# Micro_Bit_Controller_Bit.net
KiCad netlist of a schematic drawn in EAGLE
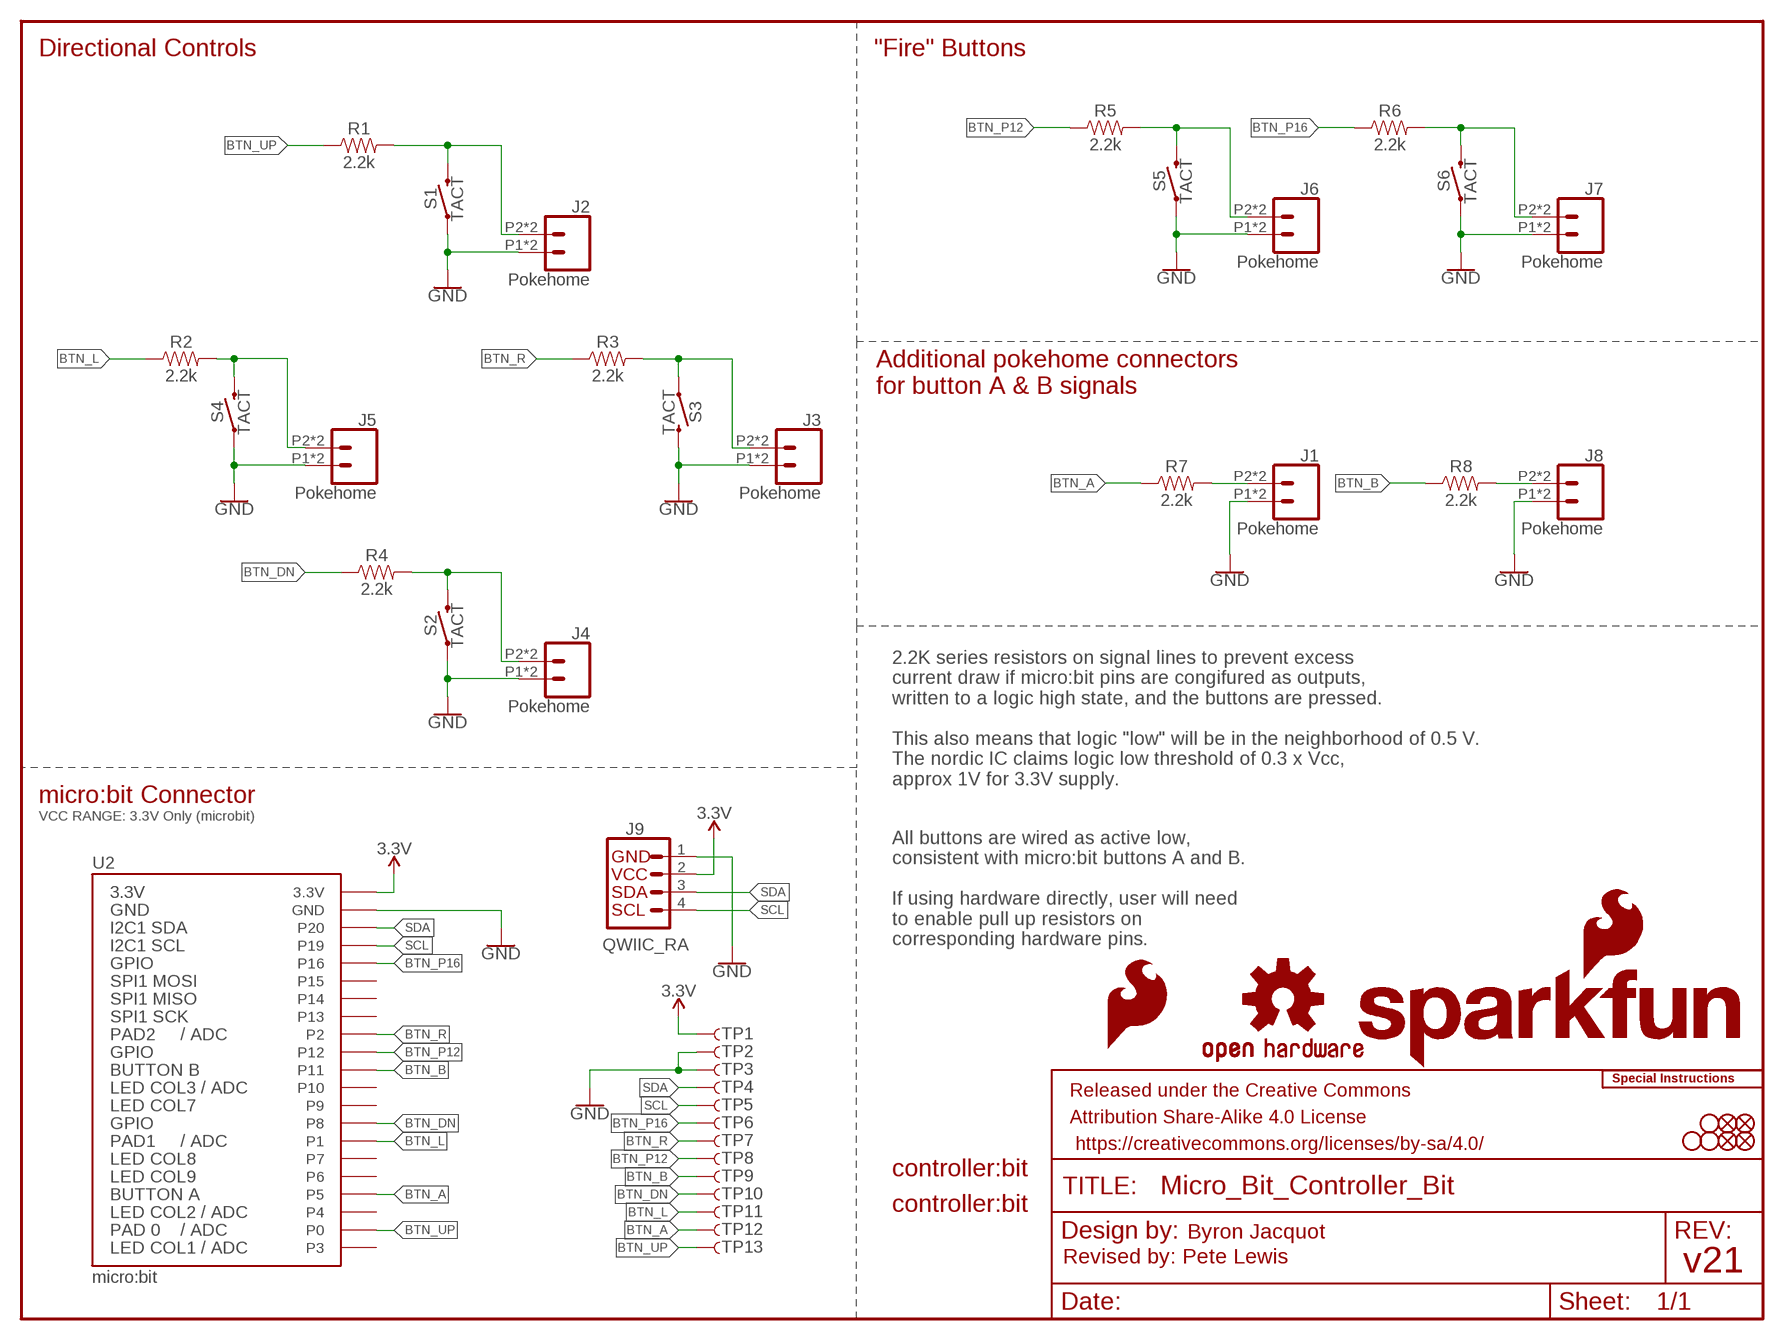
[diagram p0: schematic, sheet 1]

(export (version "E")
  (design (tool "Eeschema 10.0.6"))
  (components
    (comp (ref "FD1")
      (value "FIDUCIALUFIDUCIAL")
      (footprint "eagle-import:FIDUCIAL-MICRO")
      (libsource (lib "eagle-import") (part "FIDUCIALUFIDUCIAL"))
    )
    (comp (ref "FD2")
      (value "FIDUCIALUFIDUCIAL")
      (footprint "eagle-import:FIDUCIAL-MICRO")
      (libsource (lib "eagle-import") (part "FIDUCIALUFIDUCIAL"))
    )
    (comp (ref "FD3")
      (value "FIDUCIALUFIDUCIAL")
      (footprint "eagle-import:FIDUCIAL-MICRO")
      (libsource (lib "eagle-import") (part "FIDUCIALUFIDUCIAL"))
    )
    (comp (ref "FD4")
      (value "FIDUCIALUFIDUCIAL")
      (footprint "eagle-import:FIDUCIAL-MICRO")
      (libsource (lib "eagle-import") (part "FIDUCIALUFIDUCIAL"))
    )
    (comp (ref "FRAME1")
      (value "FRAME-LETTER")
      (footprint "eagle-import:CREATIVE_COMMONS")
      (libsource (lib "eagle-import") (part "FRAME-LETTER"))
    )
    (comp (ref "H1")
      (value "STAND-OFF")
      (footprint "eagle-import:STAND-OFF")
      (libsource (lib "eagle-import") (part "STAND-OFF"))
    )
    (comp (ref "H2")
      (value "STAND-OFF")
      (footprint "eagle-import:STAND-OFF")
      (libsource (lib "eagle-import") (part "STAND-OFF"))
    )
    (comp (ref "H3")
      (value "STAND-OFF")
      (footprint "eagle-import:STAND-OFF")
      (libsource (lib "eagle-import") (part "STAND-OFF"))
    )
    (comp (ref "J1")
      (value "Pokehome")
      (footprint "eagle-import:1X02_POKEHOME")
      (libsource (lib "eagle-import") (part "CONN_02SMALL_POKEHOME"))
    )
    (comp (ref "J2")
      (value "Pokehome")
      (footprint "eagle-import:1X02_POKEHOME")
      (libsource (lib "eagle-import") (part "CONN_02SMALL_POKEHOME"))
    )
    (comp (ref "J3")
      (value "Pokehome")
      (footprint "eagle-import:1X02_POKEHOME")
      (libsource (lib "eagle-import") (part "CONN_02SMALL_POKEHOME"))
    )
    (comp (ref "J4")
      (value "Pokehome")
      (footprint "eagle-import:1X02_POKEHOME")
      (libsource (lib "eagle-import") (part "CONN_02SMALL_POKEHOME"))
    )
    (comp (ref "J5")
      (value "Pokehome")
      (footprint "eagle-import:1X02_POKEHOME")
      (libsource (lib "eagle-import") (part "CONN_02SMALL_POKEHOME"))
    )
    (comp (ref "J6")
      (value "Pokehome")
      (footprint "eagle-import:1X02_POKEHOME")
      (libsource (lib "eagle-import") (part "CONN_02SMALL_POKEHOME"))
    )
    (comp (ref "J7")
      (value "Pokehome")
      (footprint "eagle-import:1X02_POKEHOME")
      (libsource (lib "eagle-import") (part "CONN_02SMALL_POKEHOME"))
    )
    (comp (ref "J8")
      (value "Pokehome")
      (footprint "eagle-import:1X02_POKEHOME")
      (libsource (lib "eagle-import") (part "CONN_02SMALL_POKEHOME"))
    )
    (comp (ref "J9")
      (value "QWIIC_RA")
      (footprint "eagle-import:JST04_1MM_RA")
      (libsource (lib "eagle-import") (part "QWIIC_CONNECTORJS-1MM"))
    )
    (comp (ref "LOGO1")
      (value "SFE_LOGO_FLAME.2_INCH")
      (footprint "eagle-import:SFE_LOGO_FLAME_.2")
      (libsource (lib "eagle-import") (part "SFE_LOGO_FLAME.2_INCH"))
    )
    (comp (ref "LOGO2")
      (value "OSHW-LOGOL")
      (footprint "eagle-import:OSHW-LOGO-L")
      (libsource (lib "eagle-import") (part "OSHW-LOGOL"))
    )
    (comp (ref "LOGO3")
      (value "SFE_LOGO_NAME_FLAME.3_INCH")
      (footprint "eagle-import:SFE_LOGO_NAME_FLAME_.3")
      (libsource (lib "eagle-import") (part "SFE_LOGO_NAME_FLAME.3_INCH"))
    )
    (comp (ref "R1")
      (value "2.2k")
      (footprint "eagle-import:0603")
      (libsource (lib "eagle-import") (part "2.2KOHM-0603-1/10W-1%"))
    )
    (comp (ref "R2")
      (value "2.2k")
      (footprint "eagle-import:0603")
      (libsource (lib "eagle-import") (part "2.2KOHM-0603-1/10W-1%"))
    )
    (comp (ref "R3")
      (value "2.2k")
      (footprint "eagle-import:0603")
      (libsource (lib "eagle-import") (part "2.2KOHM-0603-1/10W-1%"))
    )
    (comp (ref "R4")
      (value "2.2k")
      (footprint "eagle-import:0603")
      (libsource (lib "eagle-import") (part "2.2KOHM-0603-1/10W-1%"))
    )
    (comp (ref "R5")
      (value "2.2k")
      (footprint "eagle-import:0603")
      (libsource (lib "eagle-import") (part "2.2KOHM-0603-1/10W-1%"))
    )
    (comp (ref "R6")
      (value "2.2k")
      (footprint "eagle-import:0603")
      (libsource (lib "eagle-import") (part "2.2KOHM-0603-1/10W-1%"))
    )
    (comp (ref "R7")
      (value "2.2k")
      (footprint "eagle-import:0603")
      (libsource (lib "eagle-import") (part "2.2KOHM-0603-1/10W-1%"))
    )
    (comp (ref "R8")
      (value "2.2k")
      (footprint "eagle-import:0603")
      (libsource (lib "eagle-import") (part "2.2KOHM-0603-1/10W-1%"))
    )
    (comp (ref "S1")
      (value "TACT")
      (footprint "eagle-import:TACTILE_SWITCH_SMD_12MM")
      (libsource (lib "eagle-import") (part "MOMENTARY-SWITCH-SPST-SMD-12MM"))
    )
    (comp (ref "S2")
      (value "TACT")
      (footprint "eagle-import:TACTILE_SWITCH_SMD_12MM")
      (libsource (lib "eagle-import") (part "MOMENTARY-SWITCH-SPST-SMD-12MM"))
    )
    (comp (ref "S3")
      (value "TACT")
      (footprint "eagle-import:TACTILE_SWITCH_SMD_12MM")
      (libsource (lib "eagle-import") (part "MOMENTARY-SWITCH-SPST-SMD-12MM"))
    )
    (comp (ref "S4")
      (value "TACT")
      (footprint "eagle-import:TACTILE_SWITCH_SMD_12MM")
      (libsource (lib "eagle-import") (part "MOMENTARY-SWITCH-SPST-SMD-12MM"))
    )
    (comp (ref "S5")
      (value "TACT")
      (footprint "eagle-import:TACTILE_SWITCH_SMD_12MM")
      (libsource (lib "eagle-import") (part "MOMENTARY-SWITCH-SPST-SMD-12MM"))
    )
    (comp (ref "S6")
      (value "TACT")
      (footprint "eagle-import:TACTILE_SWITCH_SMD_12MM")
      (libsource (lib "eagle-import") (part "MOMENTARY-SWITCH-SPST-SMD-12MM"))
    )
    (comp (ref "TP1")
      (value "TEST-POINT3X5")
      (footprint "eagle-import:PAD.03X.05")
      (libsource (lib "eagle-import") (part "TEST-POINT3X5"))
    )
    (comp (ref "TP2")
      (value "TEST-POINT3X5")
      (footprint "eagle-import:PAD.03X.05")
      (libsource (lib "eagle-import") (part "TEST-POINT3X5"))
    )
    (comp (ref "TP3")
      (value "TEST-POINT3X5")
      (footprint "eagle-import:PAD.03X.05")
      (libsource (lib "eagle-import") (part "TEST-POINT3X5"))
    )
    (comp (ref "TP4")
      (value "TEST-POINT3X5")
      (footprint "eagle-import:PAD.03X.05")
      (libsource (lib "eagle-import") (part "TEST-POINT3X5"))
    )
    (comp (ref "TP5")
      (value "TEST-POINT3X5")
      (footprint "eagle-import:PAD.03X.05")
      (libsource (lib "eagle-import") (part "TEST-POINT3X5"))
    )
    (comp (ref "TP6")
      (value "TEST-POINT3X5")
      (footprint "eagle-import:PAD.03X.05")
      (libsource (lib "eagle-import") (part "TEST-POINT3X5"))
    )
    (comp (ref "TP7")
      (value "TEST-POINT3X5")
      (footprint "eagle-import:PAD.03X.05")
      (libsource (lib "eagle-import") (part "TEST-POINT3X5"))
    )
    (comp (ref "TP8")
      (value "TEST-POINT3X5")
      (footprint "eagle-import:PAD.03X.05")
      (libsource (lib "eagle-import") (part "TEST-POINT3X5"))
    )
    (comp (ref "TP9")
      (value "TEST-POINT3X5")
      (footprint "eagle-import:PAD.03X.05")
      (libsource (lib "eagle-import") (part "TEST-POINT3X5"))
    )
    (comp (ref "TP10")
      (value "TEST-POINT3X5")
      (footprint "eagle-import:PAD.03X.05")
      (libsource (lib "eagle-import") (part "TEST-POINT3X5"))
    )
    (comp (ref "TP11")
      (value "TEST-POINT3X5")
      (footprint "eagle-import:PAD.03X.05")
      (libsource (lib "eagle-import") (part "TEST-POINT3X5"))
    )
    (comp (ref "TP12")
      (value "TEST-POINT3X5")
      (footprint "eagle-import:PAD.03X.05")
      (libsource (lib "eagle-import") (part "TEST-POINT3X5"))
    )
    (comp (ref "TP13")
      (value "TEST-POINT3X5")
      (footprint "eagle-import:PAD.03X.05")
      (libsource (lib "eagle-import") (part "TEST-POINT3X5"))
    )
    (comp (ref "U$1")
      (value "SPECIAL_INSTRUCTIONS-ORDERING")
      (footprint "eagle-import:ORDERING_INSTRUCTIONS")
      (libsource (lib "eagle-import") (part "SPECIAL_INSTRUCTIONS-ORDERING"))
    )
    (comp (ref "U$3")
      (value "LOGO-CONTROLLER_BIT")
      (footprint "eagle-import:LOGO-CONTROLLER_BIT")
      (libsource (lib "eagle-import") (part "LOGO-CONTROLLER_BIT"))
    )
    (comp (ref "U$6")
      (value "LOGO-CONTROLLER_BIT")
      (footprint "eagle-import:LOGO-CONTROLLER_BIT")
      (libsource (lib "eagle-import") (part "LOGO-CONTROLLER_BIT"))
    )
    (comp (ref "U2")
      (value "micro:bit")
      (footprint "eagle-import:MICRO_BIT-RA_SMD")
      (libsource (lib "eagle-import") (part "MICRO{colon}BIT?_RA"))
    )
  )
  (nets
    (net (code "1") (name "3.3V") (class "Default")
      (node (ref "J9") (pin "2") (pinfunction "2_2") (pintype "power_in"))
      (node (ref "TP1") (pin "P$1") (pinfunction "1_P$1") (pintype "bidirectional"))
      (node (ref "U2") (pin "P$27") (pinfunction "3.3V_P$27") (pintype "bidirectional"))
      (node (ref "U2") (pin "P$28") (pinfunction "3.3V_P$28") (pintype "bidirectional"))
      (node (ref "U2") (pin "P$29") (pinfunction "3.3V_P$29") (pintype "bidirectional"))
      (node (ref "U2") (pin "P$30") (pinfunction "3.3V_P$30") (pintype "bidirectional"))
      (node (ref "U2") (pin "P$31") (pinfunction "3.3V_P$31") (pintype "bidirectional"))
      (node (ref "U2") (pin "P$32") (pinfunction "3.3V_P$32") (pintype "bidirectional"))
    )
    (net (code "2") (name "BTN_A") (class "Default")
      (node (ref "R7") (pin "1") (pinfunction "1_1") (pintype "passive"))
      (node (ref "TP12") (pin "P$1") (pinfunction "1_P$1") (pintype "bidirectional"))
      (node (ref "U2") (pin "P$7") (pinfunction "P5_P$7") (pintype "bidirectional"))
    )
    (net (code "3") (name "BTN_B") (class "Default")
      (node (ref "R8") (pin "1") (pinfunction "1_1") (pintype "passive"))
      (node (ref "TP9") (pin "P$1") (pinfunction "1_P$1") (pintype "bidirectional"))
      (node (ref "U2") (pin "P$17") (pinfunction "P11_P$17") (pintype "bidirectional"))
    )
    (net (code "4") (name "BTN_DN") (class "Default")
      (node (ref "R4") (pin "1") (pinfunction "1_1") (pintype "passive"))
      (node (ref "TP10") (pin "P$1") (pinfunction "1_P$1") (pintype "bidirectional"))
      (node (ref "U2") (pin "P$14") (pinfunction "P8_P$14") (pintype "bidirectional"))
    )
    (net (code "5") (name "BTN_L") (class "Default")
      (node (ref "R2") (pin "1") (pinfunction "1_1") (pintype "passive"))
      (node (ref "TP11") (pin "P$1") (pinfunction "1_P$1") (pintype "bidirectional"))
      (node (ref "U2") (pin "P$10") (pinfunction "P1_P$10") (pintype "bidirectional"))
      (node (ref "U2") (pin "P$11") (pinfunction "P1_P$11") (pintype "bidirectional"))
      (node (ref "U2") (pin "P$12") (pinfunction "P1_P$12") (pintype "bidirectional"))
      (node (ref "U2") (pin "P$13") (pinfunction "P1_P$13") (pintype "bidirectional"))
    )
    (net (code "6") (name "BTN_P12") (class "Default")
      (node (ref "R5") (pin "1") (pinfunction "1_1") (pintype "passive"))
      (node (ref "TP8") (pin "P$1") (pinfunction "1_P$1") (pintype "bidirectional"))
      (node (ref "U2") (pin "P$18") (pinfunction "P12_P$18") (pintype "bidirectional"))
    )
    (net (code "7") (name "BTN_P16") (class "Default")
      (node (ref "R6") (pin "1") (pinfunction "1_1") (pintype "passive"))
      (node (ref "TP6") (pin "P$1") (pinfunction "1_P$1") (pintype "bidirectional"))
      (node (ref "U2") (pin "P$26") (pinfunction "P16_P$26") (pintype "bidirectional"))
    )
    (net (code "8") (name "BTN_R") (class "Default")
      (node (ref "R3") (pin "1") (pinfunction "1_1") (pintype "passive"))
      (node (ref "TP7") (pin "P$1") (pinfunction "1_P$1") (pintype "bidirectional"))
      (node (ref "U2") (pin "P$19") (pinfunction "P2_P$19") (pintype "bidirectional"))
      (node (ref "U2") (pin "P$20") (pinfunction "P2_P$20") (pintype "bidirectional"))
      (node (ref "U2") (pin "P$21") (pinfunction "P2_P$21") (pintype "bidirectional"))
      (node (ref "U2") (pin "P$22") (pinfunction "P2_P$22") (pintype "bidirectional"))
    )
    (net (code "9") (name "BTN_UP") (class "Default")
      (node (ref "R1") (pin "1") (pinfunction "1_1") (pintype "passive"))
      (node (ref "TP13") (pin "P$1") (pinfunction "1_P$1") (pintype "bidirectional"))
      (node (ref "U2") (pin "P$2") (pinfunction "P0_P$2") (pintype "bidirectional"))
      (node (ref "U2") (pin "P$3") (pinfunction "P0_P$3") (pintype "bidirectional"))
      (node (ref "U2") (pin "P$4") (pinfunction "P0_P$4") (pintype "bidirectional"))
      (node (ref "U2") (pin "P$5") (pinfunction "P0_P$5") (pintype "bidirectional"))
    )
    (net (code "10") (name "GND") (class "Default")
      (node (ref "J1") (pin "P1") (pinfunction "1_P1") (pintype "passive"))
      (node (ref "J1") (pin "P3") (pinfunction "1_P3") (pintype "passive"))
      (node (ref "J2") (pin "P1") (pinfunction "1_P1") (pintype "passive"))
      (node (ref "J2") (pin "P3") (pinfunction "1_P3") (pintype "passive"))
      (node (ref "J3") (pin "P1") (pinfunction "1_P1") (pintype "passive"))
      (node (ref "J3") (pin "P3") (pinfunction "1_P3") (pintype "passive"))
      (node (ref "J4") (pin "P1") (pinfunction "1_P1") (pintype "passive"))
      (node (ref "J4") (pin "P3") (pinfunction "1_P3") (pintype "passive"))
      (node (ref "J5") (pin "P1") (pinfunction "1_P1") (pintype "passive"))
      (node (ref "J5") (pin "P3") (pinfunction "1_P3") (pintype "passive"))
      (node (ref "J6") (pin "P1") (pinfunction "1_P1") (pintype "passive"))
      (node (ref "J6") (pin "P3") (pinfunction "1_P3") (pintype "passive"))
      (node (ref "J7") (pin "P1") (pinfunction "1_P1") (pintype "passive"))
      (node (ref "J7") (pin "P3") (pinfunction "1_P3") (pintype "passive"))
      (node (ref "J8") (pin "P1") (pinfunction "1_P1") (pintype "passive"))
      (node (ref "J8") (pin "P3") (pinfunction "1_P3") (pintype "passive"))
      (node (ref "J9") (pin "1") (pinfunction "1_1") (pintype "power_in"))
      (node (ref "S1") (pin "1") (pinfunction "1_1") (pintype "passive"))
      (node (ref "S2") (pin "1") (pinfunction "1_1") (pintype "passive"))
      (node (ref "S3") (pin "3") (pinfunction "2_3") (pintype "passive"))
      (node (ref "S4") (pin "1") (pinfunction "1_1") (pintype "passive"))
      (node (ref "S5") (pin "1") (pinfunction "1_1") (pintype "passive"))
      (node (ref "S6") (pin "1") (pinfunction "1_1") (pintype "passive"))
      (node (ref "TP2") (pin "P$1") (pinfunction "1_P$1") (pintype "bidirectional"))
      (node (ref "TP3") (pin "P$1") (pinfunction "1_P$1") (pintype "bidirectional"))
      (node (ref "U2") (pin "P$35") (pinfunction "GND_P$35") (pintype "bidirectional"))
      (node (ref "U2") (pin "P$36") (pinfunction "GND_P$36") (pintype "bidirectional"))
      (node (ref "U2") (pin "P$37") (pinfunction "GND_P$37") (pintype "bidirectional"))
      (node (ref "U2") (pin "P$38") (pinfunction "GND_P$38") (pintype "bidirectional"))
      (node (ref "U2") (pin "P$39") (pinfunction "GND_P$39") (pintype "bidirectional"))
      (node (ref "U2") (pin "P$40") (pinfunction "GND_P$40") (pintype "bidirectional"))
    )
    (net (code "11") (name "Net-(J1-2-PadP2)") (class "Default")
      (node (ref "J1") (pin "P2") (pinfunction "2_P2") (pintype "passive"))
      (node (ref "J1") (pin "P4") (pinfunction "2_P4") (pintype "passive"))
      (node (ref "R7") (pin "2") (pinfunction "2_2") (pintype "passive"))
    )
    (net (code "12") (name "Net-(J3-2-PadP2)") (class "Default")
      (node (ref "J3") (pin "P2") (pinfunction "2_P2") (pintype "passive"))
      (node (ref "J3") (pin "P4") (pinfunction "2_P4") (pintype "passive"))
      (node (ref "R3") (pin "2") (pinfunction "2_2") (pintype "passive"))
      (node (ref "S3") (pin "1") (pinfunction "1_1") (pintype "passive"))
    )
    (net (code "13") (name "Net-(J8-2-PadP2)") (class "Default")
      (node (ref "J8") (pin "P2") (pinfunction "2_P2") (pintype "passive"))
      (node (ref "J8") (pin "P4") (pinfunction "2_P4") (pintype "passive"))
      (node (ref "R8") (pin "2") (pinfunction "2_2") (pintype "passive"))
    )
    (net (code "14") (name "Net-(S1-2)") (class "Default")
      (node (ref "J2") (pin "P2") (pinfunction "2_P2") (pintype "passive"))
      (node (ref "J2") (pin "P4") (pinfunction "2_P4") (pintype "passive"))
      (node (ref "R1") (pin "2") (pinfunction "2_2") (pintype "passive"))
      (node (ref "S1") (pin "3") (pinfunction "2_3") (pintype "passive"))
    )
    (net (code "15") (name "Net-(S2-2)") (class "Default")
      (node (ref "J4") (pin "P2") (pinfunction "2_P2") (pintype "passive"))
      (node (ref "J4") (pin "P4") (pinfunction "2_P4") (pintype "passive"))
      (node (ref "R4") (pin "2") (pinfunction "2_2") (pintype "passive"))
      (node (ref "S2") (pin "3") (pinfunction "2_3") (pintype "passive"))
    )
    (net (code "16") (name "Net-(S4-2)") (class "Default")
      (node (ref "J5") (pin "P2") (pinfunction "2_P2") (pintype "passive"))
      (node (ref "J5") (pin "P4") (pinfunction "2_P4") (pintype "passive"))
      (node (ref "R2") (pin "2") (pinfunction "2_2") (pintype "passive"))
      (node (ref "S4") (pin "3") (pinfunction "2_3") (pintype "passive"))
    )
    (net (code "17") (name "Net-(S5-2)") (class "Default")
      (node (ref "J6") (pin "P2") (pinfunction "2_P2") (pintype "passive"))
      (node (ref "J6") (pin "P4") (pinfunction "2_P4") (pintype "passive"))
      (node (ref "R5") (pin "2") (pinfunction "2_2") (pintype "passive"))
      (node (ref "S5") (pin "3") (pinfunction "2_3") (pintype "passive"))
    )
    (net (code "18") (name "Net-(S6-2)") (class "Default")
      (node (ref "J7") (pin "P2") (pinfunction "2_P2") (pintype "passive"))
      (node (ref "J7") (pin "P4") (pinfunction "2_P4") (pintype "passive"))
      (node (ref "R6") (pin "2") (pinfunction "2_2") (pintype "passive"))
      (node (ref "S6") (pin "3") (pinfunction "2_3") (pintype "passive"))
    )
    (net (code "19") (name "SCL") (class "Default")
      (node (ref "J9") (pin "4") (pinfunction "4_4") (pintype "passive"))
      (node (ref "TP5") (pin "P$1") (pinfunction "1_P$1") (pintype "bidirectional"))
      (node (ref "U2") (pin "P$33") (pinfunction "P19_P$33") (pintype "bidirectional"))
    )
    (net (code "20") (name "SDA") (class "Default")
      (node (ref "J9") (pin "3") (pinfunction "3_3") (pintype "passive"))
      (node (ref "TP4") (pin "P$1") (pinfunction "1_P$1") (pintype "bidirectional"))
      (node (ref "U2") (pin "P$34") (pinfunction "P20_P$34") (pintype "bidirectional"))
    )
    (net (code "21") (name "unconnected-(U2-P3-PadP$1)") (class "Default")
      (node (ref "U2") (pin "P$1") (pinfunction "P3_P$1") (pintype "bidirectional"))
    )
    (net (code "22") (name "unconnected-(U2-P4-PadP$6)") (class "Default")
      (node (ref "U2") (pin "P$6") (pinfunction "P4_P$6") (pintype "bidirectional"))
    )
    (net (code "23") (name "unconnected-(U2-P6-PadP$8)") (class "Default")
      (node (ref "U2") (pin "P$8") (pinfunction "P6_P$8") (pintype "bidirectional"))
    )
    (net (code "24") (name "unconnected-(U2-P7-PadP$9)") (class "Default")
      (node (ref "U2") (pin "P$9") (pinfunction "P7_P$9") (pintype "bidirectional"))
    )
    (net (code "25") (name "unconnected-(U2-P9-PadP$15)") (class "Default")
      (node (ref "U2") (pin "P$15") (pinfunction "P9_P$15") (pintype "bidirectional"))
    )
    (net (code "26") (name "unconnected-(U2-P10-PadP$16)") (class "Default")
      (node (ref "U2") (pin "P$16") (pinfunction "P10_P$16") (pintype "bidirectional"))
    )
    (net (code "27") (name "unconnected-(U2-P13-PadP$23)") (class "Default")
      (node (ref "U2") (pin "P$23") (pinfunction "P13_P$23") (pintype "bidirectional"))
    )
    (net (code "28") (name "unconnected-(U2-P14-PadP$24)") (class "Default")
      (node (ref "U2") (pin "P$24") (pinfunction "P14_P$24") (pintype "bidirectional"))
    )
    (net (code "29") (name "unconnected-(U2-P15-PadP$25)") (class "Default")
      (node (ref "U2") (pin "P$25") (pinfunction "P15_P$25") (pintype "bidirectional"))
    )
  )
)
